# External_Connections.net
KiCad netlist of a schematic drawn in Altium Designer
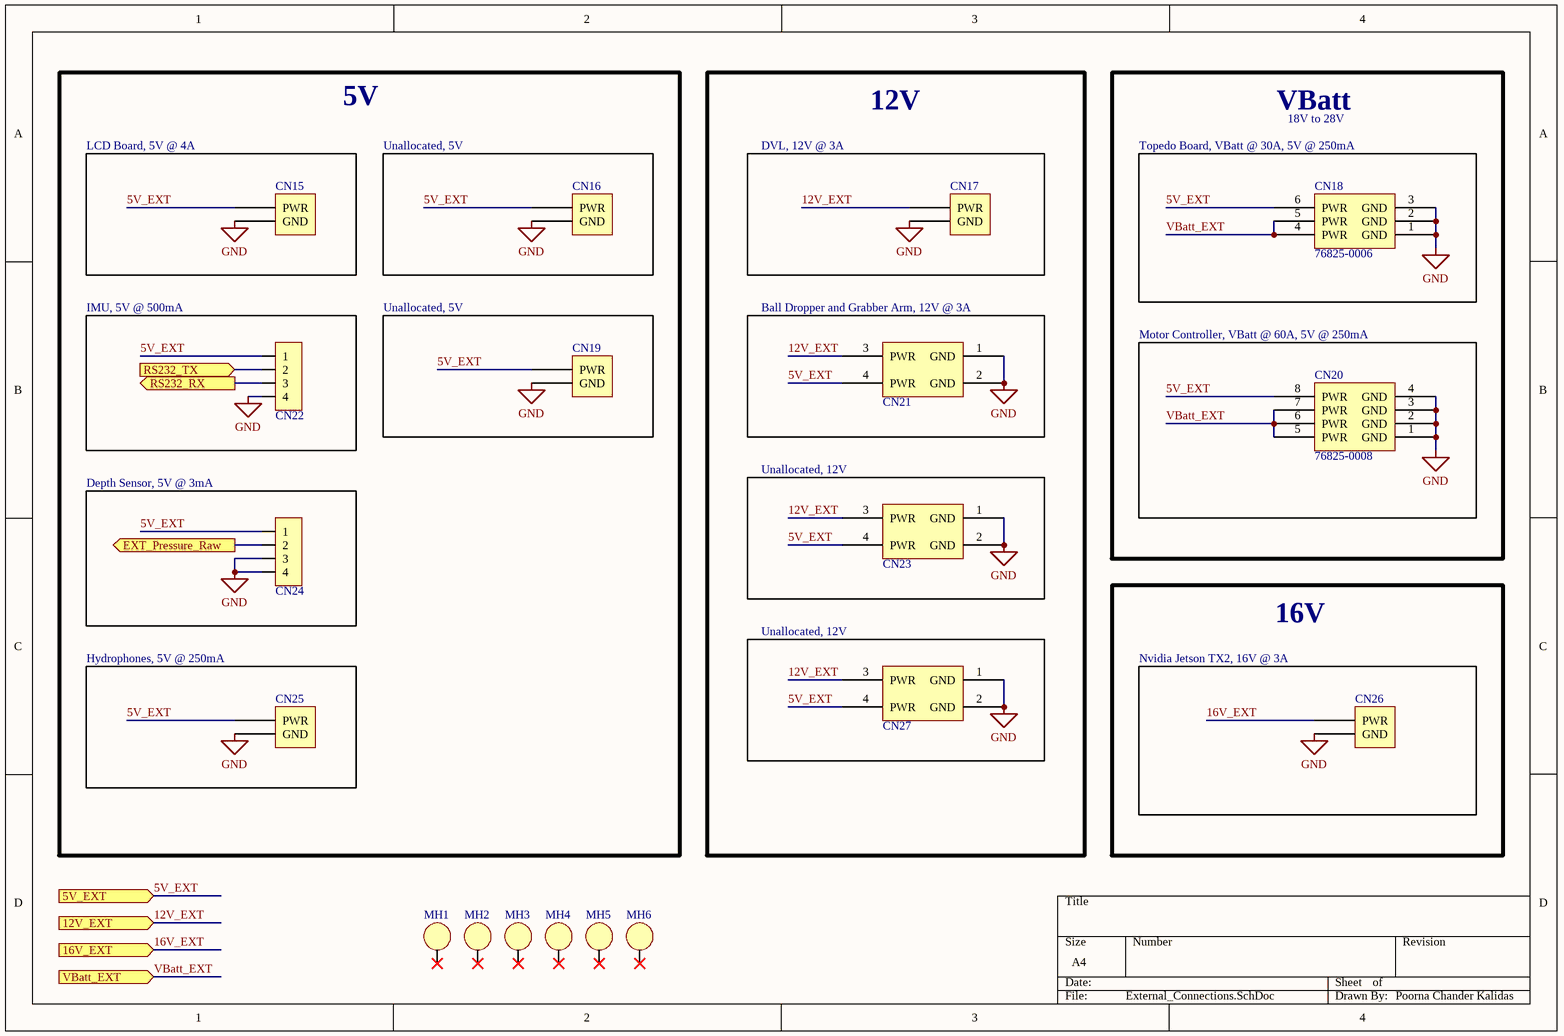
[diagram p0: External_Connections.SchDoc]

(export (version "E")
  (design (tool "Eeschema 10.0.6"))
  (components
    (comp (ref "CN15")
      (value "Header, Female, 1x2, Right Angle, Pitch 0.118\" (3.00mm), THT")
      (footprint "New footprint 1")
      (description "Connector Header Through Hole, Right Angle 2 position")
      (libsource (lib "AUVIC") (part "Header, 1x2, Right Angle, Pitch 0.118{dblquote} (3.00mm), THT"))
    )
    (comp (ref "CN16")
      (value "Header, Female, 1x2, Right Angle, Pitch 0.118\" (3.00mm), THT")
      (footprint "New footprint 1")
      (description "Connector Header Through Hole, Right Angle 2 position")
      (libsource (lib "AUVIC") (part "Header, 1x2, Right Angle, Pitch 0.118{dblquote} (3.00mm), THT"))
    )
    (comp (ref "CN17")
      (value "Header, Female, 1x2, Right Angle, Pitch 0.118\" (3.00mm), THT")
      (footprint "New footprint 1")
      (description "Connector Header Through Hole, Right Angle 2 position")
      (libsource (lib "AUVIC") (part "Header, 1x2, Right Angle, Pitch 0.118{dblquote} (3.00mm), THT"))
    )
    (comp (ref "CN18")
      (value "76825-0006")
      (footprint "76825-0006-Footprint-1")
      (libsource (lib "AUVIC") (part "76825-0006"))
    )
    (comp (ref "CN19")
      (value "Header, Female, 1x2, Right Angle, Pitch 0.118\" (3.00mm), THT")
      (footprint "New footprint 1")
      (description "Connector Header Through Hole, Right Angle 2 position")
      (libsource (lib "AUVIC") (part "Header, 1x2, Right Angle, Pitch 0.118{dblquote} (3.00mm), THT"))
    )
    (comp (ref "CN20")
      (value "76825-0008")
      (footprint "76825-0008-Footprint-1")
      (description "MOLEX         76825-0008.             CONNECTOR, HEADER, 8POS, 2ROW, 5.7MM")
      (libsource (lib "AUVIC") (part "76825-0008"))
    )
    (comp (ref "CN21")
      (value "Header, Female, 2x2, RIght Angle, Pitch: 0.118\"  (3.00mm), THT")
      (footprint "2x2 Pitch 118mil connector")
      (description "Connector Header Through Hole, Right Angle 4 position 0.118\" (3.00mm)")
      (fields (field (name "PUBLISHER") "AUVic") (field (name "CREATED BY") "Poorna Chander Kalidas"))
      (libsource (lib "AUVIC") (part "Header, Female, 2x2, RIght Angle, Pitch{colon} 0.118{dblquote}  (3.00mm), THT"))
    )
    (comp (ref "CN22")
      (value "Header, Male, 1x4, RA, Pitch 0.1\" (2.54mm)")
      (footprint "HEADER, MALE, SHROUDED, 4x1, PITCH 0.1\" (2.54mm), RA")
      (description "Connector Header Through Hole, Right Angle 4 position 0.100\" (2.54mm)")
      (fields (field (name "CREATED BY") "Miguel Manguerra"))
      (libsource (lib "AUVIC") (part "Symbol"))
    )
    (comp (ref "CN23")
      (value "Header, Female, 2x2, RIght Angle, Pitch: 0.118\"  (3.00mm), THT")
      (footprint "2x2 Pitch 118mil connector")
      (description "Connector Header Through Hole, Right Angle 4 position 0.118\" (3.00mm)")
      (fields (field (name "PUBLISHER") "AUVic") (field (name "CREATED BY") "Poorna Chander Kalidas"))
      (libsource (lib "AUVIC") (part "Header, Female, 2x2, RIght Angle, Pitch{colon} 0.118{dblquote}  (3.00mm), THT"))
    )
    (comp (ref "CN24")
      (value "Header, Male, 1x4, RA, Pitch 0.1\" (2.54mm)")
      (footprint "HEADER, MALE, SHROUDED, 4x1, PITCH 0.1\" (2.54mm), RA")
      (description "Connector Header Through Hole, Right Angle 4 position 0.100\" (2.54mm)")
      (fields (field (name "CREATED BY") "Miguel Manguerra"))
      (libsource (lib "AUVIC") (part "Symbol"))
    )
    (comp (ref "CN25")
      (value "Header, Female, 1x2, Right Angle, Pitch 0.118\" (3.00mm), THT")
      (footprint "New footprint 1")
      (description "Connector Header Through Hole, Right Angle 2 position")
      (libsource (lib "AUVIC") (part "Header, 1x2, Right Angle, Pitch 0.118{dblquote} (3.00mm), THT"))
    )
    (comp (ref "CN26")
      (value "Header, Female, 1x2, Right Angle, Pitch 0.118\" (3.00mm), THT")
      (footprint "New footprint 1")
      (description "Connector Header Through Hole, Right Angle 2 position")
      (libsource (lib "AUVIC") (part "Header, 1x2, Right Angle, Pitch 0.118{dblquote} (3.00mm), THT"))
    )
    (comp (ref "CN27")
      (value "Header, Female, 2x2, RIght Angle, Pitch: 0.118\"  (3.00mm), THT")
      (footprint "2x2 Pitch 118mil connector")
      (description "Connector Header Through Hole, Right Angle 4 position 0.118\" (3.00mm)")
      (fields (field (name "PUBLISHER") "AUVic") (field (name "CREATED BY") "Poorna Chander Kalidas"))
      (libsource (lib "AUVIC") (part "Header, Female, 2x2, RIght Angle, Pitch{colon} 0.118{dblquote}  (3.00mm), THT"))
    )
    (comp (ref "MH1")
      (value "Mount_Hole_3mm")
      (footprint "Mount-Hole_3mm")
      (description "Mounting hold for M3 hex standoff")
      (libsource (lib "AUVIC") (part "Mount_Hole_3mm"))
    )
    (comp (ref "MH2")
      (value "Mount_Hole_3mm")
      (footprint "Mount-Hole_3mm")
      (description "Mounting hold for M3 hex standoff")
      (libsource (lib "AUVIC") (part "Mount_Hole_3mm"))
    )
    (comp (ref "MH3")
      (value "Mount_Hole_3mm")
      (footprint "Mount-Hole_3mm")
      (description "Mounting hold for M3 hex standoff")
      (libsource (lib "AUVIC") (part "Mount_Hole_3mm"))
    )
    (comp (ref "MH4")
      (value "Mount_Hole_3mm")
      (footprint "Mount-Hole_3mm")
      (description "Mounting hold for M3 hex standoff")
      (libsource (lib "AUVIC") (part "Mount_Hole_3mm"))
    )
    (comp (ref "MH5")
      (value "Mount_Hole_3mm")
      (footprint "Mount-Hole_3mm")
      (description "Mounting hold for M3 hex standoff")
      (libsource (lib "AUVIC") (part "Mount_Hole_3mm"))
    )
    (comp (ref "MH6")
      (value "Mount_Hole_3mm")
      (footprint "Mount-Hole_3mm")
      (description "Mounting hold for M3 hex standoff")
      (libsource (lib "AUVIC") (part "Mount_Hole_3mm"))
    )
  )
  (nets
    (net (code "1") (name "/5V_EXT") (class "Default")
      (node (ref "CN15") (pin "2") (pinfunction "PWR_2") (pintype "passive"))
      (node (ref "CN16") (pin "2") (pinfunction "PWR_2") (pintype "passive"))
      (node (ref "CN18") (pin "6") (pinfunction "PWR_6") (pintype "passive"))
      (node (ref "CN19") (pin "2") (pinfunction "PWR_2") (pintype "passive"))
      (node (ref "CN20") (pin "8") (pinfunction "PWR_8") (pintype "passive"))
      (node (ref "CN21") (pin "4") (pinfunction "PWR_4") (pintype "passive"))
      (node (ref "CN22") (pin "1") (pinfunction "1_1") (pintype "passive"))
      (node (ref "CN23") (pin "4") (pinfunction "PWR_4") (pintype "passive"))
      (node (ref "CN24") (pin "1") (pinfunction "1_1") (pintype "passive"))
      (node (ref "CN25") (pin "2") (pinfunction "PWR_2") (pintype "passive"))
      (node (ref "CN27") (pin "4") (pinfunction "PWR_4") (pintype "passive"))
    )
    (net (code "2") (name "/12V_EXT") (class "Default")
      (node (ref "CN17") (pin "2") (pinfunction "PWR_2") (pintype "passive"))
      (node (ref "CN21") (pin "3") (pinfunction "PWR_3") (pintype "passive"))
      (node (ref "CN23") (pin "3") (pinfunction "PWR_3") (pintype "passive"))
      (node (ref "CN27") (pin "3") (pinfunction "PWR_3") (pintype "passive"))
    )
    (net (code "3") (name "/16V_EXT") (class "Default")
      (node (ref "CN26") (pin "2") (pinfunction "PWR_2") (pintype "passive"))
    )
    (net (code "4") (name "/EXT_Pressure_Raw") (class "Default")
      (node (ref "CN24") (pin "2") (pinfunction "2_2") (pintype "passive"))
    )
    (net (code "5") (name "/RS232_RX") (class "Default")
      (node (ref "CN22") (pin "3") (pinfunction "3_3") (pintype "passive"))
    )
    (net (code "6") (name "/RS232_TX") (class "Default")
      (node (ref "CN22") (pin "2") (pinfunction "2_2") (pintype "passive"))
    )
    (net (code "7") (name "/VBatt_EXT") (class "Default")
      (node (ref "CN18") (pin "4") (pinfunction "PWR_4") (pintype "passive"))
      (node (ref "CN18") (pin "5") (pinfunction "PWR_5") (pintype "passive"))
      (node (ref "CN20") (pin "5") (pinfunction "PWR_5") (pintype "passive"))
      (node (ref "CN20") (pin "6") (pinfunction "PWR_6") (pintype "passive"))
      (node (ref "CN20") (pin "7") (pinfunction "PWR_7") (pintype "passive"))
    )
    (net (code "8") (name "GND") (class "Default")
      (node (ref "CN15") (pin "1") (pinfunction "GND_1") (pintype "passive"))
      (node (ref "CN16") (pin "1") (pinfunction "GND_1") (pintype "passive"))
      (node (ref "CN17") (pin "1") (pinfunction "GND_1") (pintype "passive"))
      (node (ref "CN18") (pin "1") (pinfunction "GND_1") (pintype "passive"))
      (node (ref "CN18") (pin "2") (pinfunction "GND_2") (pintype "passive"))
      (node (ref "CN18") (pin "3") (pinfunction "GND_3") (pintype "passive"))
      (node (ref "CN19") (pin "1") (pinfunction "GND_1") (pintype "passive"))
      (node (ref "CN20") (pin "1") (pinfunction "GND_1") (pintype "passive"))
      (node (ref "CN20") (pin "2") (pinfunction "GND_2") (pintype "passive"))
      (node (ref "CN20") (pin "3") (pinfunction "GND_3") (pintype "passive"))
      (node (ref "CN20") (pin "4") (pinfunction "GND_4") (pintype "passive"))
      (node (ref "CN21") (pin "1") (pinfunction "GND_1") (pintype "passive"))
      (node (ref "CN21") (pin "2") (pinfunction "GND_2") (pintype "passive"))
      (node (ref "CN22") (pin "4") (pinfunction "4_4") (pintype "passive"))
      (node (ref "CN23") (pin "1") (pinfunction "GND_1") (pintype "passive"))
      (node (ref "CN23") (pin "2") (pinfunction "GND_2") (pintype "passive"))
      (node (ref "CN24") (pin "3") (pinfunction "3_3") (pintype "passive"))
      (node (ref "CN24") (pin "4") (pinfunction "4_4") (pintype "passive"))
      (node (ref "CN25") (pin "1") (pinfunction "GND_1") (pintype "passive"))
      (node (ref "CN26") (pin "1") (pinfunction "GND_1") (pintype "passive"))
      (node (ref "CN27") (pin "1") (pinfunction "GND_1") (pintype "passive"))
      (node (ref "CN27") (pin "2") (pinfunction "GND_2") (pintype "passive"))
    )
    (net (code "9") (name "unconnected-(MH1-Pad1)") (class "Default")
      (node (ref "MH1") (pin "1") (pinfunction "1_1") (pintype "passive+no_connect"))
    )
    (net (code "10") (name "unconnected-(MH2-Pad1)") (class "Default")
      (node (ref "MH2") (pin "1") (pinfunction "1_1") (pintype "passive+no_connect"))
    )
    (net (code "11") (name "unconnected-(MH3-Pad1)") (class "Default")
      (node (ref "MH3") (pin "1") (pinfunction "1_1") (pintype "passive+no_connect"))
    )
    (net (code "12") (name "unconnected-(MH4-Pad1)") (class "Default")
      (node (ref "MH4") (pin "1") (pinfunction "1_1") (pintype "passive+no_connect"))
    )
    (net (code "13") (name "unconnected-(MH5-Pad1)") (class "Default")
      (node (ref "MH5") (pin "1") (pinfunction "1_1") (pintype "passive+no_connect"))
    )
    (net (code "14") (name "unconnected-(MH6-Pad1)") (class "Default")
      (node (ref "MH6") (pin "1") (pinfunction "1_1") (pintype "passive+no_connect"))
    )
  )
)
